# PCB-SSB-1x2.net
KiCad netlist of a schematic drawn in EAGLE
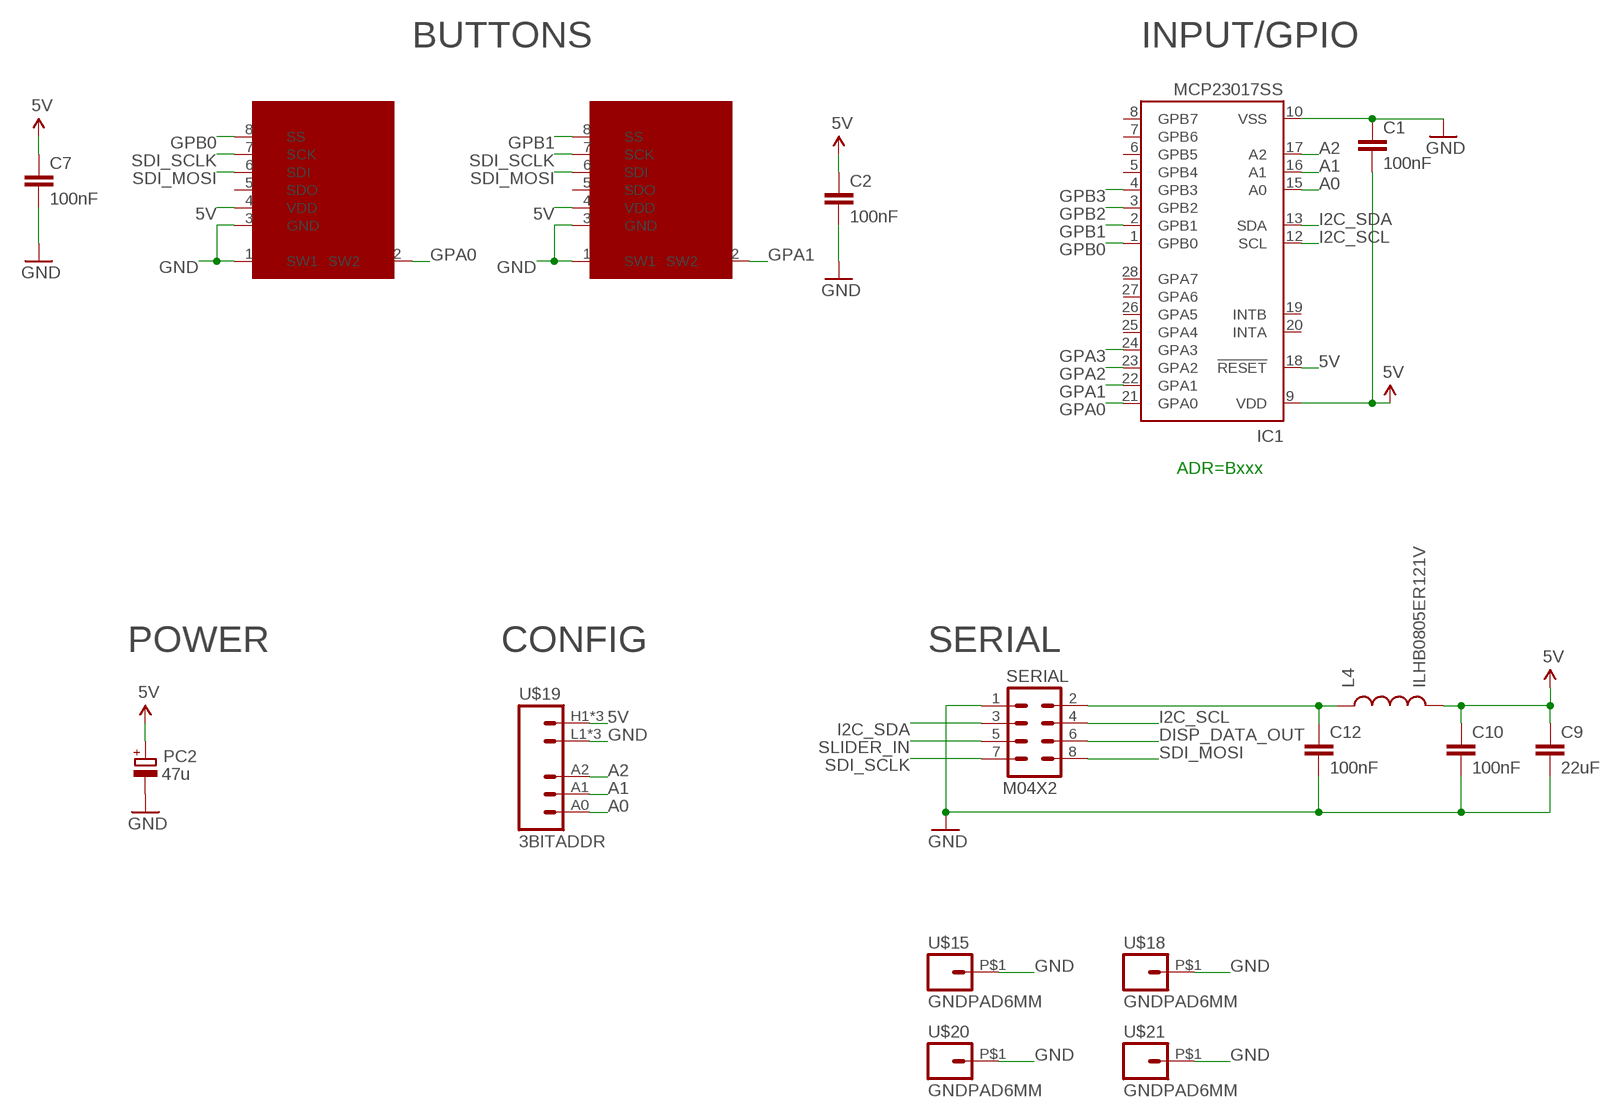
[diagram p0: schematic, sheet 1]

(export (version "E")
  (design (tool "Eeschema 10.0.6"))
  (components
    (comp (ref "C1")
      (value "100nF")
      (footprint "eagle-import:0603-CAP")
      (libsource (lib "eagle-import") (part "CAP0603-CAP"))
    )
    (comp (ref "C2")
      (value "100nF")
      (footprint "eagle-import:0603-CAP")
      (libsource (lib "eagle-import") (part "CAP0603-CAP"))
    )
    (comp (ref "C7")
      (value "100nF")
      (footprint "eagle-import:0603-CAP")
      (libsource (lib "eagle-import") (part "CAP0603-CAP"))
    )
    (comp (ref "C9")
      (value "22uF")
      (footprint "eagle-import:0805")
      (libsource (lib "eagle-import") (part "CAP0805"))
    )
    (comp (ref "C10")
      (value "100nF")
      (footprint "eagle-import:0603-CAP")
      (libsource (lib "eagle-import") (part "CAP0603-CAP"))
    )
    (comp (ref "C12")
      (value "100nF")
      (footprint "eagle-import:0603-CAP")
      (libsource (lib "eagle-import") (part "CAP0603-CAP"))
    )
    (comp (ref "IC1")
      (value "MCP23017SS")
      (footprint "eagle-import:SSOP28")
      (fields
        (field (name "MF") "MICROCHIP")
        (field (name "MPN") "MCP23017-E/SS")
        (field (name "MPN_1") "MCP23017-E/SS")
        (field (name "OC_FARNELL") "1467674")
        (field (name "OC_NEWARK") "31K2960")
      )
      (libsource (lib "eagle-import") (part "MCP23017SS"))
    )
    (comp (ref "L4")
      (value "ILHB0805ER121V")
      (footprint "eagle-import:0805")
      (libsource (lib "eagle-import") (part "INDUCTOR0805"))
    )
    (comp (ref "PC2")
      (value "47u")
      (footprint "eagle-import:PANASONIC_D")
      (libsource (lib "eagle-import") (part "CPOL-EUD"))
    )
    (comp (ref "SERIAL")
      (value "M04X2")
      (footprint "eagle-import:2X4")
      (libsource (lib "eagle-import") (part "M04X2"))
    )
    (comp (ref "SSW1")
      (value "SMART_SWITCHSMART_SWITCH_8PIN")
      (footprint "eagle-import:SMART_SWITCH")
      (libsource (lib "eagle-import") (part "SMART_SWITCHSMART_SWITCH_8PIN"))
    )
    (comp (ref "SSW2")
      (value "SMART_SWITCHSMART_SWITCH_8PIN")
      (footprint "eagle-import:SMART_SWITCH")
      (libsource (lib "eagle-import") (part "SMART_SWITCHSMART_SWITCH_8PIN"))
    )
    (comp (ref "U$15")
      (value "GNDPAD6MM")
      (footprint "eagle-import:3.2MMPAD6MM")
      (libsource (lib "eagle-import") (part "GNDPAD6MM"))
    )
    (comp (ref "U$18")
      (value "GNDPAD6MM")
      (footprint "eagle-import:3.2MMPAD6MM")
      (libsource (lib "eagle-import") (part "GNDPAD6MM"))
    )
    (comp (ref "U$19")
      (value "3BITADDR")
      (footprint "eagle-import:3BITADDR")
      (libsource (lib "eagle-import") (part "3BITADDR"))
    )
    (comp (ref "U$20")
      (value "GNDPAD6MM")
      (footprint "eagle-import:3.2MMPAD6MM")
      (libsource (lib "eagle-import") (part "GNDPAD6MM"))
    )
    (comp (ref "U$21")
      (value "GNDPAD6MM")
      (footprint "eagle-import:3.2MMPAD6MM")
      (libsource (lib "eagle-import") (part "GNDPAD6MM"))
    )
  )
  (nets
    (net (code "1") (name "/A0") (class "Default")
      (node (ref "IC1") (pin "15") (pinfunction "A0_15") (pintype "input"))
      (node (ref "U$19") (pin "A0") (pinfunction "A0_A0") (pintype "passive"))
    )
    (net (code "2") (name "/A1") (class "Default")
      (node (ref "IC1") (pin "16") (pinfunction "A1_16") (pintype "input"))
      (node (ref "U$19") (pin "A1") (pinfunction "A1_A1") (pintype "passive"))
    )
    (net (code "3") (name "/A2") (class "Default")
      (node (ref "IC1") (pin "17") (pinfunction "A2_17") (pintype "input"))
      (node (ref "U$19") (pin "A2") (pinfunction "A2_A2") (pintype "passive"))
    )
    (net (code "4") (name "/DISP_DATA_OUT") (class "Default")
      (node (ref "SERIAL") (pin "6") (pinfunction "6_6") (pintype "passive"))
    )
    (net (code "5") (name "/GPA0") (class "Default")
      (node (ref "IC1") (pin "21") (pinfunction "GPA0_21") (pintype "bidirectional"))
      (node (ref "SSW1") (pin "2") (pinfunction "SW2_2") (pintype "bidirectional"))
    )
    (net (code "6") (name "/GPA1") (class "Default")
      (node (ref "IC1") (pin "22") (pinfunction "GPA1_22") (pintype "bidirectional"))
      (node (ref "SSW2") (pin "2") (pinfunction "SW2_2") (pintype "bidirectional"))
    )
    (net (code "7") (name "/GPA2") (class "Default")
      (node (ref "IC1") (pin "23") (pinfunction "GPA2_23") (pintype "bidirectional"))
    )
    (net (code "8") (name "/GPA3") (class "Default")
      (node (ref "IC1") (pin "24") (pinfunction "GPA3_24") (pintype "bidirectional"))
    )
    (net (code "9") (name "/GPB0") (class "Default")
      (node (ref "IC1") (pin "1") (pinfunction "GPB0_1") (pintype "bidirectional"))
      (node (ref "SSW1") (pin "8") (pinfunction "SS_8") (pintype "bidirectional"))
    )
    (net (code "10") (name "/GPB1") (class "Default")
      (node (ref "IC1") (pin "2") (pinfunction "GPB1_2") (pintype "bidirectional"))
      (node (ref "SSW2") (pin "8") (pinfunction "SS_8") (pintype "bidirectional"))
    )
    (net (code "11") (name "/GPB2") (class "Default")
      (node (ref "IC1") (pin "3") (pinfunction "GPB2_3") (pintype "bidirectional"))
    )
    (net (code "12") (name "/GPB3") (class "Default")
      (node (ref "IC1") (pin "4") (pinfunction "GPB3_4") (pintype "bidirectional"))
    )
    (net (code "13") (name "/I2C_SCL") (class "Default")
      (node (ref "IC1") (pin "12") (pinfunction "SCL_12") (pintype "input"))
      (node (ref "SERIAL") (pin "4") (pinfunction "4_4") (pintype "passive"))
    )
    (net (code "14") (name "/I2C_SDA") (class "Default")
      (node (ref "IC1") (pin "13") (pinfunction "SDA_13") (pintype "bidirectional"))
      (node (ref "SERIAL") (pin "3") (pinfunction "3_3") (pintype "passive"))
    )
    (net (code "15") (name "/SDI_MOSI") (class "Default")
      (node (ref "SERIAL") (pin "8") (pinfunction "8_8") (pintype "passive"))
      (node (ref "SSW1") (pin "6") (pinfunction "SDI_6") (pintype "bidirectional"))
      (node (ref "SSW2") (pin "6") (pinfunction "SDI_6") (pintype "bidirectional"))
    )
    (net (code "16") (name "/SDI_SCLK") (class "Default")
      (node (ref "SERIAL") (pin "7") (pinfunction "7_7") (pintype "passive"))
      (node (ref "SSW1") (pin "7") (pinfunction "SCK_7") (pintype "bidirectional"))
      (node (ref "SSW2") (pin "7") (pinfunction "SCK_7") (pintype "bidirectional"))
    )
    (net (code "17") (name "/SLIDER_IN") (class "Default")
      (node (ref "SERIAL") (pin "5") (pinfunction "5_5") (pintype "passive"))
    )
    (net (code "18") (name "5V") (class "Default")
      (node (ref "C1") (pin "2") (pinfunction "2_2") (pintype "passive"))
      (node (ref "C10") (pin "1") (pinfunction "1_1") (pintype "passive"))
      (node (ref "C2") (pin "1") (pinfunction "1_1") (pintype "passive"))
      (node (ref "C7") (pin "1") (pinfunction "1_1") (pintype "passive"))
      (node (ref "C9") (pin "1") (pinfunction "1_1") (pintype "passive"))
      (node (ref "IC1") (pin "18") (pinfunction "~{RESET}_18") (pintype "input"))
      (node (ref "IC1") (pin "9") (pinfunction "VDD_9") (pintype "power_in"))
      (node (ref "L4") (pin "2") (pinfunction "2_2") (pintype "passive"))
      (node (ref "PC2") (pin "+") (pinfunction "+_+") (pintype "passive"))
      (node (ref "SSW1") (pin "4") (pinfunction "VDD_4") (pintype "bidirectional"))
      (node (ref "SSW2") (pin "4") (pinfunction "VDD_4") (pintype "bidirectional"))
      (node (ref "U$19") (pin "H1") (pinfunction "VCC_H1") (pintype "passive"))
      (node (ref "U$19") (pin "H2") (pinfunction "VCC_H2") (pintype "passive"))
      (node (ref "U$19") (pin "H3") (pinfunction "VCC_H3") (pintype "passive"))
    )
    (net (code "19") (name "GND") (class "Default")
      (node (ref "C1") (pin "1") (pinfunction "1_1") (pintype "passive"))
      (node (ref "C10") (pin "2") (pinfunction "2_2") (pintype "passive"))
      (node (ref "C12") (pin "2") (pinfunction "2_2") (pintype "passive"))
      (node (ref "C2") (pin "2") (pinfunction "2_2") (pintype "passive"))
      (node (ref "C7") (pin "2") (pinfunction "2_2") (pintype "passive"))
      (node (ref "C9") (pin "2") (pinfunction "2_2") (pintype "passive"))
      (node (ref "IC1") (pin "10") (pinfunction "VSS_10") (pintype "power_in"))
      (node (ref "PC2") (pin "-") (pinfunction "-_-") (pintype "passive"))
      (node (ref "SERIAL") (pin "1") (pinfunction "1_1") (pintype "passive"))
      (node (ref "SSW1") (pin "1") (pinfunction "SW1_1") (pintype "bidirectional"))
      (node (ref "SSW1") (pin "3") (pinfunction "GND_3") (pintype "bidirectional"))
      (node (ref "SSW2") (pin "1") (pinfunction "SW1_1") (pintype "bidirectional"))
      (node (ref "SSW2") (pin "3") (pinfunction "GND_3") (pintype "bidirectional"))
      (node (ref "U$15") (pin "P$1") (pinfunction "1_P$1") (pintype "passive"))
      (node (ref "U$18") (pin "P$1") (pinfunction "1_P$1") (pintype "passive"))
      (node (ref "U$19") (pin "L1") (pinfunction "GND_L1") (pintype "passive"))
      (node (ref "U$19") (pin "L2") (pinfunction "GND_L2") (pintype "passive"))
      (node (ref "U$19") (pin "L3") (pinfunction "GND_L3") (pintype "passive"))
      (node (ref "U$20") (pin "P$1") (pinfunction "1_P$1") (pintype "passive"))
      (node (ref "U$21") (pin "P$1") (pinfunction "1_P$1") (pintype "passive"))
    )
    (net (code "20") (name "Net-(C12-Pad1)") (class "Default")
      (node (ref "C12") (pin "1") (pinfunction "1_1") (pintype "passive"))
      (node (ref "L4") (pin "1") (pinfunction "1_1") (pintype "passive"))
      (node (ref "SERIAL") (pin "2") (pinfunction "2_2") (pintype "passive"))
    )
    (net (code "21") (name "unconnected-(IC1-GPA4-Pad25)") (class "Default")
      (node (ref "IC1") (pin "25") (pinfunction "GPA4_25") (pintype "bidirectional"))
    )
    (net (code "22") (name "unconnected-(IC1-GPA5-Pad26)") (class "Default")
      (node (ref "IC1") (pin "26") (pinfunction "GPA5_26") (pintype "bidirectional"))
    )
    (net (code "23") (name "unconnected-(IC1-GPA6-Pad27)") (class "Default")
      (node (ref "IC1") (pin "27") (pinfunction "GPA6_27") (pintype "bidirectional"))
    )
    (net (code "24") (name "unconnected-(IC1-GPA7-Pad28)") (class "Default")
      (node (ref "IC1") (pin "28") (pinfunction "GPA7_28") (pintype "bidirectional"))
    )
    (net (code "25") (name "unconnected-(IC1-GPB4-Pad5)") (class "Default")
      (node (ref "IC1") (pin "5") (pinfunction "GPB4_5") (pintype "bidirectional"))
    )
    (net (code "26") (name "unconnected-(IC1-GPB5-Pad6)") (class "Default")
      (node (ref "IC1") (pin "6") (pinfunction "GPB5_6") (pintype "bidirectional"))
    )
    (net (code "27") (name "unconnected-(IC1-GPB6-Pad7)") (class "Default")
      (node (ref "IC1") (pin "7") (pinfunction "GPB6_7") (pintype "bidirectional"))
    )
    (net (code "28") (name "unconnected-(IC1-GPB7-Pad8)") (class "Default")
      (node (ref "IC1") (pin "8") (pinfunction "GPB7_8") (pintype "bidirectional"))
    )
    (net (code "29") (name "unconnected-(IC1-INTA-Pad20)") (class "Default")
      (node (ref "IC1") (pin "20") (pinfunction "INTA_20") (pintype "output"))
    )
    (net (code "30") (name "unconnected-(IC1-INTB-Pad19)") (class "Default")
      (node (ref "IC1") (pin "19") (pinfunction "INTB_19") (pintype "output"))
    )
    (net (code "31") (name "unconnected-(SSW1-SDO-Pad5)") (class "Default")
      (node (ref "SSW1") (pin "5") (pinfunction "SDO_5") (pintype "bidirectional"))
    )
    (net (code "32") (name "unconnected-(SSW2-SDO-Pad5)") (class "Default")
      (node (ref "SSW2") (pin "5") (pinfunction "SDO_5") (pintype "bidirectional"))
    )
  )
)
